# SCH_PoC_Bluetooth_Jao.net
KiCad netlist of a schematic drawn in EasyEDA
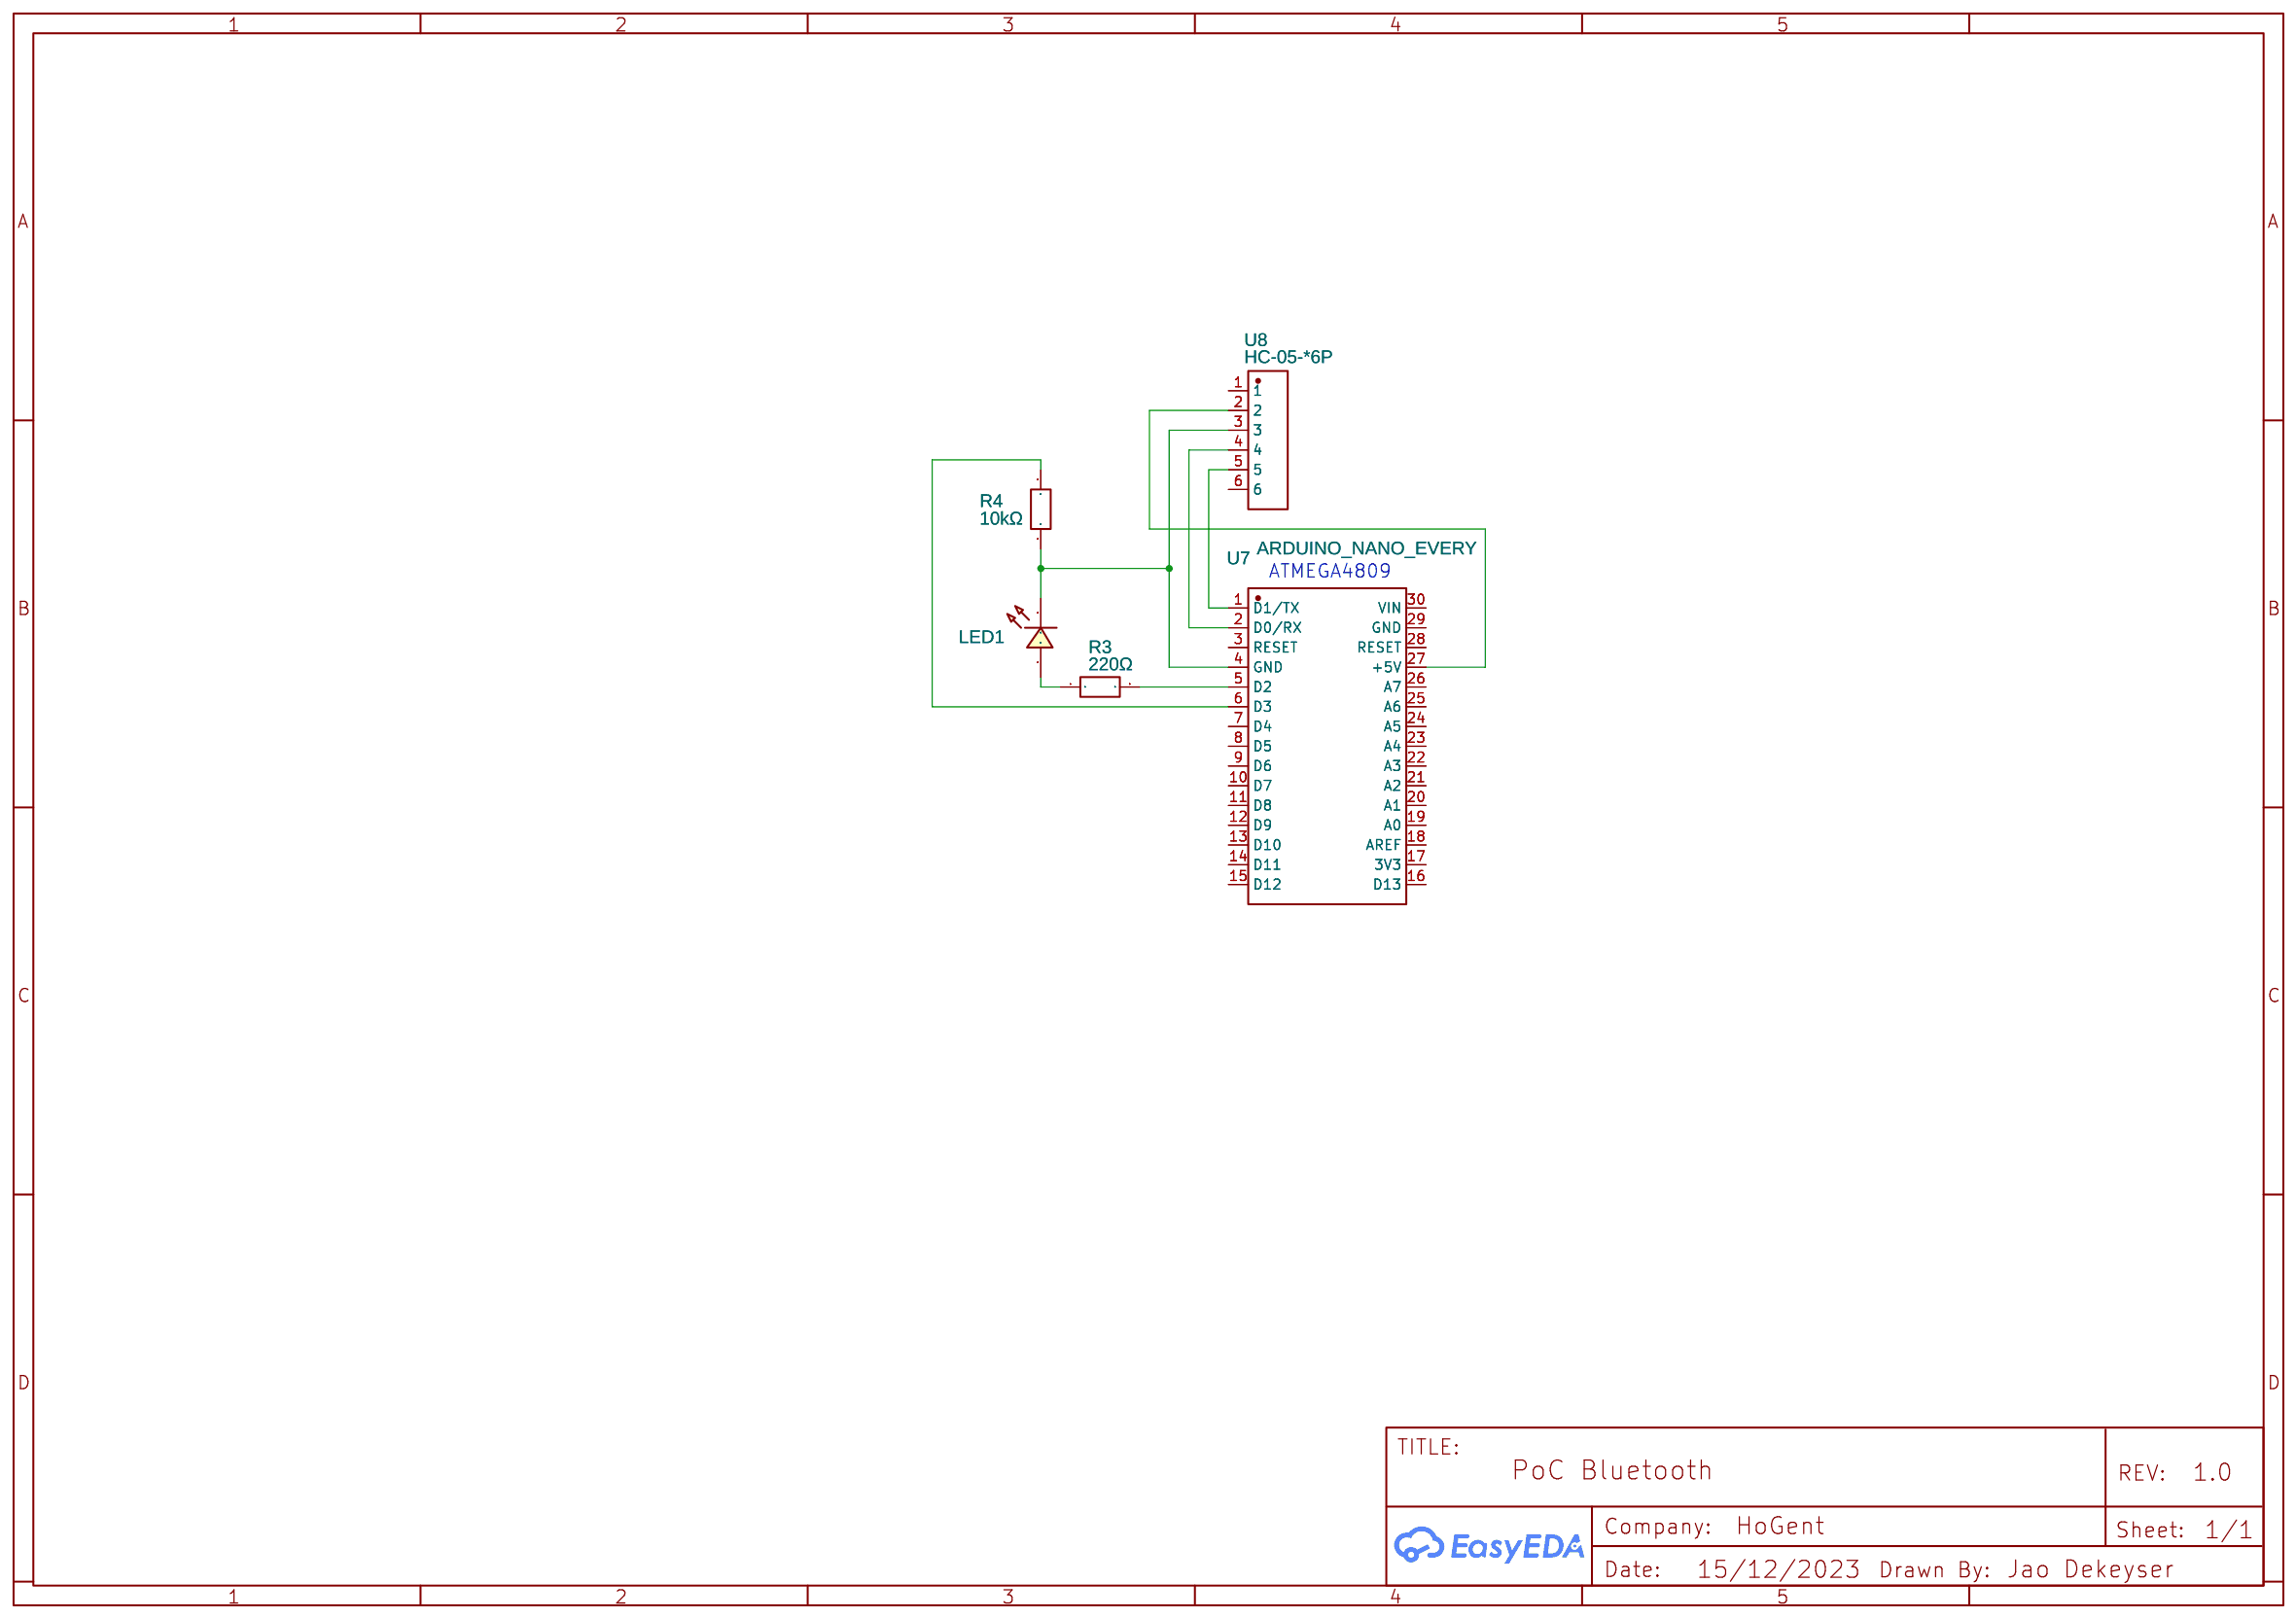
[diagram p0: schematic sheet]

(export (version "E")
  (design (tool "Eeschema 10.0.6"))
  (components
    (comp (ref "LED1")
      (value "LED-TH-5mm_R")
      (fields
        (field (name "Manufacturer Part") "333-2SURD/S530-A3")
        (field (name "Manufacturer") "EVERLIGHT(台湾亿光)")
      )
      (libsource (lib "") (part "LED-TH-5mm_R"))
    )
    (comp (ref "R3")
      (value "220Ω")
      (libsource (lib "") (part "AXIAL RESISTOR 220 OHM - TH_BD2.3-L6.0-P10.00-D0.4_1"))
    )
    (comp (ref "R4")
      (value "10kΩ")
      (libsource (lib "") (part "AXIAL RESISTOR 220 OHM - TH_BD2.3-L6.0-P10.00-D0.4"))
    )
    (comp (ref "U7")
      (value "ARDUINO_NANO_EVERY")
      (fields (field (name "Manufacturer Part") "ARDUINO_NANO"))
      (libsource (lib "") (part "ARDUINO_NANO"))
    )
    (comp (ref "U8")
      (value "HC-05-*6P")
      (fields (field (name "Manufacturer Part") "HC-05_排母*6P"))
      (libsource (lib "") (part "HC-05-*6P"))
    )
  )
  (nets
    (net (code "1") (name "Net-(LED1-Pad1)") (class "Default")
      (node (ref "LED1") (pin "1") (pinfunction "1_1") (pintype "unspecified"))
      (node (ref "R3") (pin "1") (pinfunction "1_1") (pintype "unspecified"))
    )
    (net (code "2") (name "Net-(LED1-Pad2)") (class "Default")
      (node (ref "LED1") (pin "2") (pinfunction "2_2") (pintype "unspecified"))
      (node (ref "R4") (pin "1") (pinfunction "1_1") (pintype "unspecified"))
      (node (ref "U7") (pin "4") (pinfunction "GND_4") (pintype "unspecified"))
      (node (ref "U8") (pin "3") (pinfunction "3_3") (pintype "unspecified"))
    )
    (net (code "3") (name "Net-(U7-+5V)") (class "Default")
      (node (ref "U7") (pin "27") (pinfunction "+5V_27") (pintype "unspecified"))
      (node (ref "U8") (pin "2") (pinfunction "2_2") (pintype "unspecified"))
    )
    (net (code "4") (name "Net-(U7-D0{slash}RX)") (class "Default")
      (node (ref "U7") (pin "2") (pinfunction "D0/RX_2") (pintype "unspecified"))
      (node (ref "U8") (pin "4") (pinfunction "4_4") (pintype "unspecified"))
    )
    (net (code "5") (name "Net-(U7-D1{slash}TX)") (class "Default")
      (node (ref "U7") (pin "1") (pinfunction "D1/TX_1") (pintype "unspecified"))
      (node (ref "U8") (pin "5") (pinfunction "5_5") (pintype "unspecified"))
    )
    (net (code "6") (name "Net-(U7-D2)") (class "Default")
      (node (ref "R3") (pin "2") (pinfunction "2_2") (pintype "unspecified"))
      (node (ref "U7") (pin "5") (pinfunction "D2_5") (pintype "unspecified"))
    )
    (net (code "7") (name "Net-(U7-D3)") (class "Default")
      (node (ref "R4") (pin "2") (pinfunction "2_2") (pintype "unspecified"))
      (node (ref "U7") (pin "6") (pinfunction "D3_6") (pintype "unspecified"))
    )
    (net (code "8") (name "unconnected-(U7-3V3-Pad17)") (class "Default")
      (node (ref "U7") (pin "17") (pinfunction "3V3_17") (pintype "unspecified"))
    )
    (net (code "9") (name "unconnected-(U7-A0-Pad19)") (class "Default")
      (node (ref "U7") (pin "19") (pinfunction "A0_19") (pintype "unspecified"))
    )
    (net (code "10") (name "unconnected-(U7-A1-Pad20)") (class "Default")
      (node (ref "U7") (pin "20") (pinfunction "A1_20") (pintype "unspecified"))
    )
    (net (code "11") (name "unconnected-(U7-A2-Pad21)") (class "Default")
      (node (ref "U7") (pin "21") (pinfunction "A2_21") (pintype "unspecified"))
    )
    (net (code "12") (name "unconnected-(U7-A3-Pad22)") (class "Default")
      (node (ref "U7") (pin "22") (pinfunction "A3_22") (pintype "unspecified"))
    )
    (net (code "13") (name "unconnected-(U7-A4-Pad23)") (class "Default")
      (node (ref "U7") (pin "23") (pinfunction "A4_23") (pintype "unspecified"))
    )
    (net (code "14") (name "unconnected-(U7-A5-Pad24)") (class "Default")
      (node (ref "U7") (pin "24") (pinfunction "A5_24") (pintype "unspecified"))
    )
    (net (code "15") (name "unconnected-(U7-A6-Pad25)") (class "Default")
      (node (ref "U7") (pin "25") (pinfunction "A6_25") (pintype "unspecified"))
    )
    (net (code "16") (name "unconnected-(U7-A7-Pad26)") (class "Default")
      (node (ref "U7") (pin "26") (pinfunction "A7_26") (pintype "unspecified"))
    )
    (net (code "17") (name "unconnected-(U7-AREF-Pad18)") (class "Default")
      (node (ref "U7") (pin "18") (pinfunction "AREF_18") (pintype "unspecified"))
    )
    (net (code "18") (name "unconnected-(U7-D4-Pad7)") (class "Default")
      (node (ref "U7") (pin "7") (pinfunction "D4_7") (pintype "unspecified"))
    )
    (net (code "19") (name "unconnected-(U7-D5-Pad8)") (class "Default")
      (node (ref "U7") (pin "8") (pinfunction "D5_8") (pintype "unspecified"))
    )
    (net (code "20") (name "unconnected-(U7-D6-Pad9)") (class "Default")
      (node (ref "U7") (pin "9") (pinfunction "D6_9") (pintype "unspecified"))
    )
    (net (code "21") (name "unconnected-(U7-D7-Pad10)") (class "Default")
      (node (ref "U7") (pin "10") (pinfunction "D7_10") (pintype "unspecified"))
    )
    (net (code "22") (name "unconnected-(U7-D8-Pad11)") (class "Default")
      (node (ref "U7") (pin "11") (pinfunction "D8_11") (pintype "unspecified"))
    )
    (net (code "23") (name "unconnected-(U7-D9-Pad12)") (class "Default")
      (node (ref "U7") (pin "12") (pinfunction "D9_12") (pintype "unspecified"))
    )
    (net (code "24") (name "unconnected-(U7-D10-Pad13)") (class "Default")
      (node (ref "U7") (pin "13") (pinfunction "D10_13") (pintype "unspecified"))
    )
    (net (code "25") (name "unconnected-(U7-D11-Pad14)") (class "Default")
      (node (ref "U7") (pin "14") (pinfunction "D11_14") (pintype "unspecified"))
    )
    (net (code "26") (name "unconnected-(U7-D12-Pad15)") (class "Default")
      (node (ref "U7") (pin "15") (pinfunction "D12_15") (pintype "unspecified"))
    )
    (net (code "27") (name "unconnected-(U7-D13-Pad16)") (class "Default")
      (node (ref "U7") (pin "16") (pinfunction "D13_16") (pintype "unspecified"))
    )
    (net (code "28") (name "unconnected-(U7-GND-Pad29)") (class "Default")
      (node (ref "U7") (pin "29") (pinfunction "GND_29") (pintype "unspecified"))
    )
    (net (code "29") (name "unconnected-(U7-RESET-Pad3)") (class "Default")
      (node (ref "U7") (pin "3") (pinfunction "RESET_3") (pintype "unspecified"))
    )
    (net (code "30") (name "unconnected-(U7-RESET-Pad28)") (class "Default")
      (node (ref "U7") (pin "28") (pinfunction "RESET_28") (pintype "unspecified"))
    )
    (net (code "31") (name "unconnected-(U7-VIN-Pad30)") (class "Default")
      (node (ref "U7") (pin "30") (pinfunction "VIN_30") (pintype "unspecified"))
    )
    (net (code "32") (name "unconnected-(U8-Pad1)") (class "Default")
      (node (ref "U8") (pin "1") (pinfunction "1_1") (pintype "unspecified"))
    )
    (net (code "33") (name "unconnected-(U8-Pad6)") (class "Default")
      (node (ref "U8") (pin "6") (pinfunction "6_6") (pintype "unspecified"))
    )
  )
)
